# Tortoise_Matrix_Test_Board_schematic.net
KiCad netlist of a schematic drawn in EasyEDA
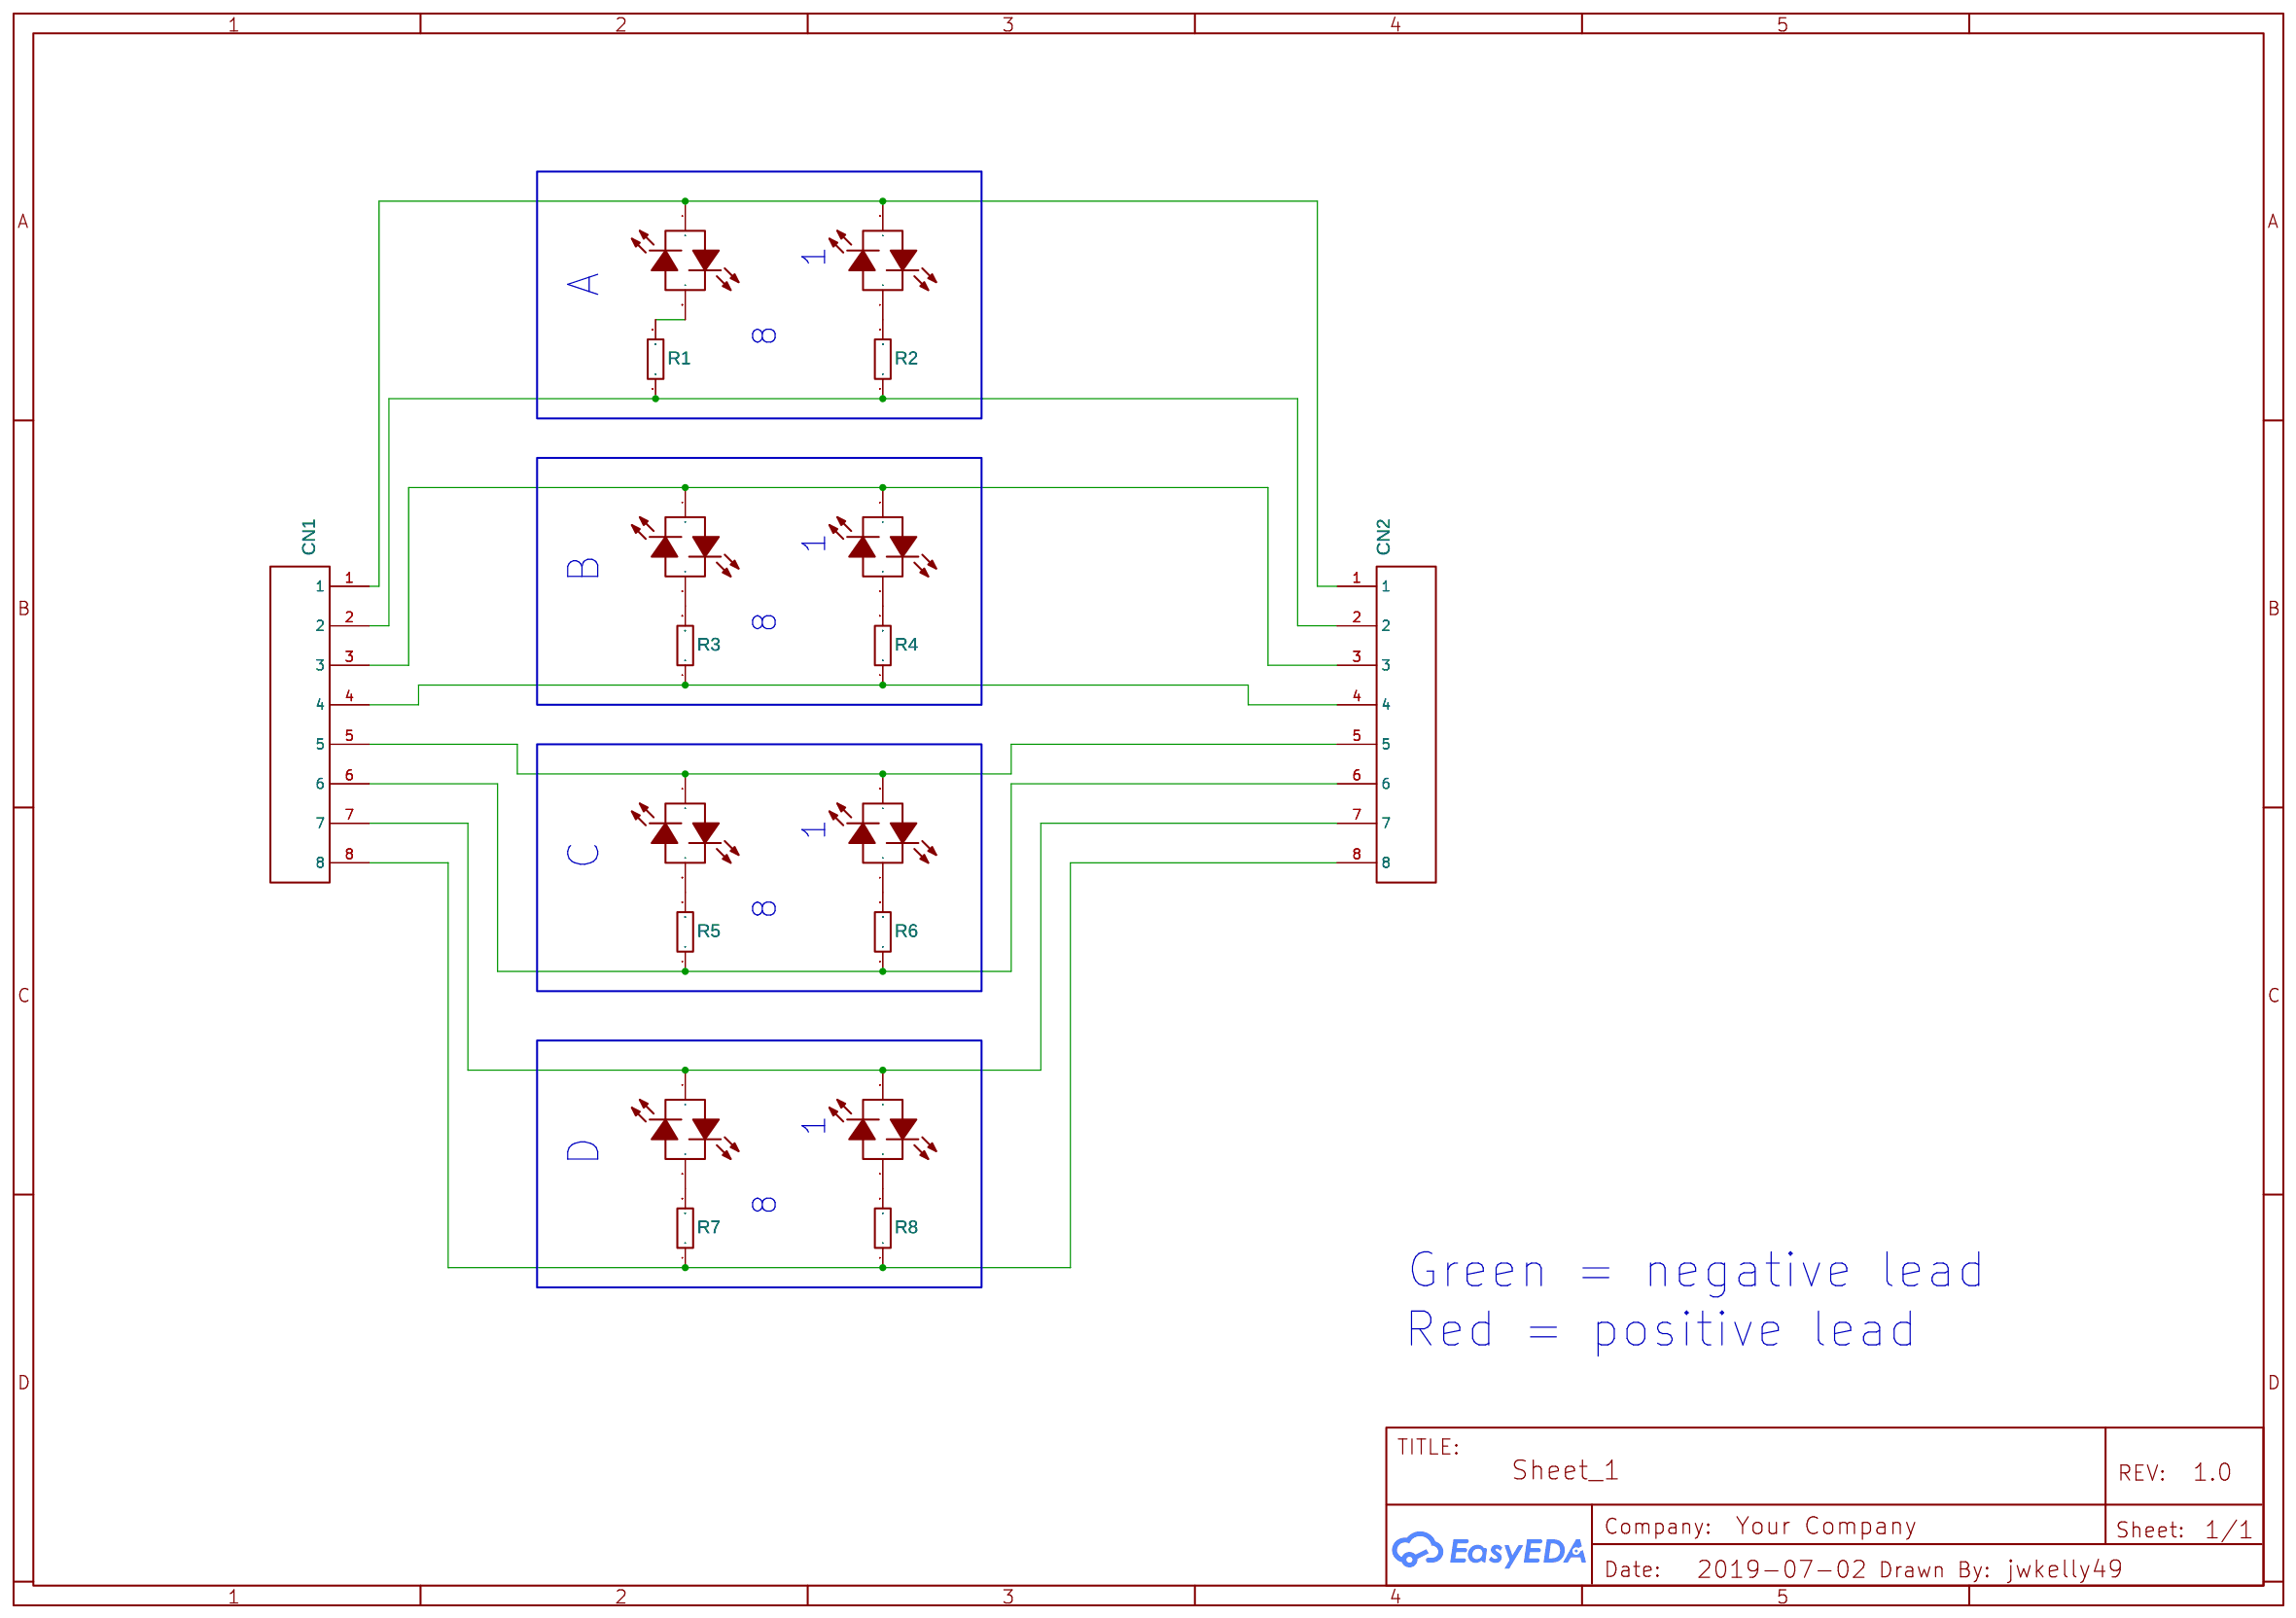
[diagram p0: schematic sheet]

(export (version "E")
  (design (tool "Eeschema 10.0.6"))
  (components
    (comp (ref "CN1")
      (value "WJ25C-B-7.62-8P-13-00A")
      (fields (field (name "BOM_Supplier Part") "C49492"))
      (libsource (lib "") (part "Unknown_160_360"))
    )
    (comp (ref "CN2")
      (value "WJ25C-B-7.62-8P-13-00A")
      (fields (field (name "BOM_Supplier Part") "C49492"))
      (libsource (lib "") (part "Unknown_690_360"))
    )
    (comp (ref "LED1")
      (value "LTL-293SJW")
      (fields (field (name "BOM_Supplier Part") "C125079"))
      (libsource (lib "") (part "Unknown_340_125"))
    )
    (comp (ref "LED2")
      (value "LTL-293SJW")
      (fields (field (name "BOM_Supplier Part") "C125079"))
      (libsource (lib "") (part "Unknown_440_125"))
    )
    (comp (ref "LED3")
      (value "LTL-293SJW")
      (fields (field (name "BOM_Supplier Part") "C125079"))
      (libsource (lib "") (part "Unknown_340_270"))
    )
    (comp (ref "LED4")
      (value "LTL-293SJW")
      (fields (field (name "BOM_Supplier Part") "C125079"))
      (libsource (lib "") (part "Unknown_440_270"))
    )
    (comp (ref "LED5")
      (value "LTL-293SJW")
      (fields (field (name "BOM_Supplier Part") "C125079"))
      (libsource (lib "") (part "Unknown_340_415"))
    )
    (comp (ref "LED6")
      (value "LTL-293SJW")
      (fields (field (name "BOM_Supplier Part") "C125079"))
      (libsource (lib "") (part "Unknown_440_415"))
    )
    (comp (ref "LED7")
      (value "LTL-293SJW")
      (fields (field (name "BOM_Supplier Part") "C125079"))
      (libsource (lib "") (part "Unknown_340_565"))
    )
    (comp (ref "LED8")
      (value "LTL-293SJW")
      (fields (field (name "BOM_Supplier Part") "C125079"))
      (libsource (lib "") (part "Unknown_440_565"))
    )
    (comp (ref "R1")
      (value "270")
      (fields
        (field (name "BOM_Manufacturer Part") "MFS1/2CCT52A2700F")
        (field (name "BOM_Supplier Part") "C202436")
      )
      (libsource (lib "") (part "MFS1/2CCT52A2700F"))
    )
    (comp (ref "R2")
      (value "270")
      (fields
        (field (name "BOM_Manufacturer Part") "MFS1/2CCT52A2700F")
        (field (name "BOM_Supplier Part") "C202436")
      )
      (libsource (lib "") (part "MFS1/2CCT52A2700F"))
    )
    (comp (ref "R3")
      (value "270")
      (fields
        (field (name "BOM_Manufacturer Part") "MFS1/2CCT52A2700F")
        (field (name "BOM_Supplier Part") "C202436")
      )
      (libsource (lib "") (part "MFS1/2CCT52A2700F"))
    )
    (comp (ref "R4")
      (value "270")
      (fields
        (field (name "BOM_Manufacturer Part") "MFS1/2CCT52A2700F")
        (field (name "BOM_Supplier Part") "C202436")
      )
      (libsource (lib "") (part "MFS1/2CCT52A2700F"))
    )
    (comp (ref "R5")
      (value "270")
      (fields
        (field (name "BOM_Manufacturer Part") "MFS1/2CCT52A2700F")
        (field (name "BOM_Supplier Part") "C202436")
      )
      (libsource (lib "") (part "MFS1/2CCT52A2700F"))
    )
    (comp (ref "R6")
      (value "270")
      (fields
        (field (name "BOM_Manufacturer Part") "MFS1/2CCT52A2700F")
        (field (name "BOM_Supplier Part") "C202436")
      )
      (libsource (lib "") (part "MFS1/2CCT52A2700F"))
    )
    (comp (ref "R7")
      (value "270")
      (fields
        (field (name "BOM_Manufacturer Part") "MFS1/2CCT52A2700F")
        (field (name "BOM_Supplier Part") "C202436")
      )
      (libsource (lib "") (part "MFS1/2CCT52A2700F"))
    )
    (comp (ref "R8")
      (value "270")
      (fields
        (field (name "BOM_Manufacturer Part") "MFS1/2CCT52A2700F")
        (field (name "BOM_Supplier Part") "C202436")
      )
      (libsource (lib "") (part "MFS1/2CCT52A2700F"))
    )
  )
  (nets
    (net (code "1") (name "Net-(CN1-Pad2)") (class "Default")
      (node (ref "CN1") (pin "2") (pinfunction "2_2") (pintype "input"))
      (node (ref "CN2") (pin "2") (pinfunction "2_2") (pintype "input"))
      (node (ref "R1") (pin "1") (pinfunction "1_1") (pintype "unspecified"))
      (node (ref "R2") (pin "1") (pinfunction "1_1") (pintype "unspecified"))
    )
    (net (code "2") (name "Net-(CN1-Pad4)") (class "Default")
      (node (ref "CN1") (pin "4") (pinfunction "4_4") (pintype "input"))
      (node (ref "CN2") (pin "4") (pinfunction "4_4") (pintype "input"))
      (node (ref "R3") (pin "1") (pinfunction "1_1") (pintype "unspecified"))
      (node (ref "R4") (pin "1") (pinfunction "1_1") (pintype "unspecified"))
    )
    (net (code "3") (name "Net-(CN1-Pad6)") (class "Default")
      (node (ref "CN1") (pin "6") (pinfunction "6_6") (pintype "input"))
      (node (ref "CN2") (pin "6") (pinfunction "6_6") (pintype "input"))
      (node (ref "R5") (pin "1") (pinfunction "1_1") (pintype "unspecified"))
      (node (ref "R6") (pin "1") (pinfunction "1_1") (pintype "unspecified"))
    )
    (net (code "4") (name "Net-(CN1-Pad8)") (class "Default")
      (node (ref "CN1") (pin "8") (pinfunction "8_8") (pintype "input"))
      (node (ref "CN2") (pin "8") (pinfunction "8_8") (pintype "input"))
      (node (ref "R7") (pin "1") (pinfunction "1_1") (pintype "unspecified"))
      (node (ref "R8") (pin "1") (pinfunction "1_1") (pintype "unspecified"))
    )
    (net (code "5") (name "Net-(LED1-A)") (class "Default")
      (node (ref "CN1") (pin "1") (pinfunction "1_1") (pintype "input"))
      (node (ref "CN2") (pin "1") (pinfunction "1_1") (pintype "input"))
      (node (ref "LED1") (pin "1") (pinfunction "A_1") (pintype "unspecified"))
      (node (ref "LED2") (pin "2") (pinfunction "K_2") (pintype "unspecified"))
    )
    (net (code "6") (name "Net-(LED1-K)") (class "Default")
      (node (ref "LED1") (pin "2") (pinfunction "K_2") (pintype "unspecified"))
      (node (ref "R1") (pin "2") (pinfunction "2_2") (pintype "unspecified"))
    )
    (net (code "7") (name "Net-(LED2-A)") (class "Default")
      (node (ref "LED2") (pin "1") (pinfunction "A_1") (pintype "unspecified"))
      (node (ref "R2") (pin "2") (pinfunction "2_2") (pintype "unspecified"))
    )
    (net (code "8") (name "Net-(LED3-A)") (class "Default")
      (node (ref "CN1") (pin "3") (pinfunction "3_3") (pintype "input"))
      (node (ref "CN2") (pin "3") (pinfunction "3_3") (pintype "input"))
      (node (ref "LED3") (pin "1") (pinfunction "A_1") (pintype "unspecified"))
      (node (ref "LED4") (pin "2") (pinfunction "K_2") (pintype "unspecified"))
    )
    (net (code "9") (name "Net-(LED3-K)") (class "Default")
      (node (ref "LED3") (pin "2") (pinfunction "K_2") (pintype "unspecified"))
      (node (ref "R3") (pin "2") (pinfunction "2_2") (pintype "unspecified"))
    )
    (net (code "10") (name "Net-(LED4-A)") (class "Default")
      (node (ref "LED4") (pin "1") (pinfunction "A_1") (pintype "unspecified"))
      (node (ref "R4") (pin "2") (pinfunction "2_2") (pintype "unspecified"))
    )
    (net (code "11") (name "Net-(LED5-A)") (class "Default")
      (node (ref "CN1") (pin "5") (pinfunction "5_5") (pintype "input"))
      (node (ref "CN2") (pin "5") (pinfunction "5_5") (pintype "input"))
      (node (ref "LED5") (pin "1") (pinfunction "A_1") (pintype "unspecified"))
      (node (ref "LED6") (pin "2") (pinfunction "K_2") (pintype "unspecified"))
    )
    (net (code "12") (name "Net-(LED5-K)") (class "Default")
      (node (ref "LED5") (pin "2") (pinfunction "K_2") (pintype "unspecified"))
      (node (ref "R5") (pin "2") (pinfunction "2_2") (pintype "unspecified"))
    )
    (net (code "13") (name "Net-(LED6-A)") (class "Default")
      (node (ref "LED6") (pin "1") (pinfunction "A_1") (pintype "unspecified"))
      (node (ref "R6") (pin "2") (pinfunction "2_2") (pintype "unspecified"))
    )
    (net (code "14") (name "Net-(LED7-A)") (class "Default")
      (node (ref "CN1") (pin "7") (pinfunction "7_7") (pintype "input"))
      (node (ref "CN2") (pin "7") (pinfunction "7_7") (pintype "input"))
      (node (ref "LED7") (pin "1") (pinfunction "A_1") (pintype "unspecified"))
      (node (ref "LED8") (pin "2") (pinfunction "K_2") (pintype "unspecified"))
    )
    (net (code "15") (name "Net-(LED7-K)") (class "Default")
      (node (ref "LED7") (pin "2") (pinfunction "K_2") (pintype "unspecified"))
      (node (ref "R7") (pin "2") (pinfunction "2_2") (pintype "unspecified"))
    )
    (net (code "16") (name "Net-(LED8-A)") (class "Default")
      (node (ref "LED8") (pin "1") (pinfunction "A_1") (pintype "unspecified"))
      (node (ref "R8") (pin "2") (pinfunction "2_2") (pintype "unspecified"))
    )
  )
)
